# LM61495Q3_PINOUT.net
KiCad netlist of a schematic drawn in Altium Designer
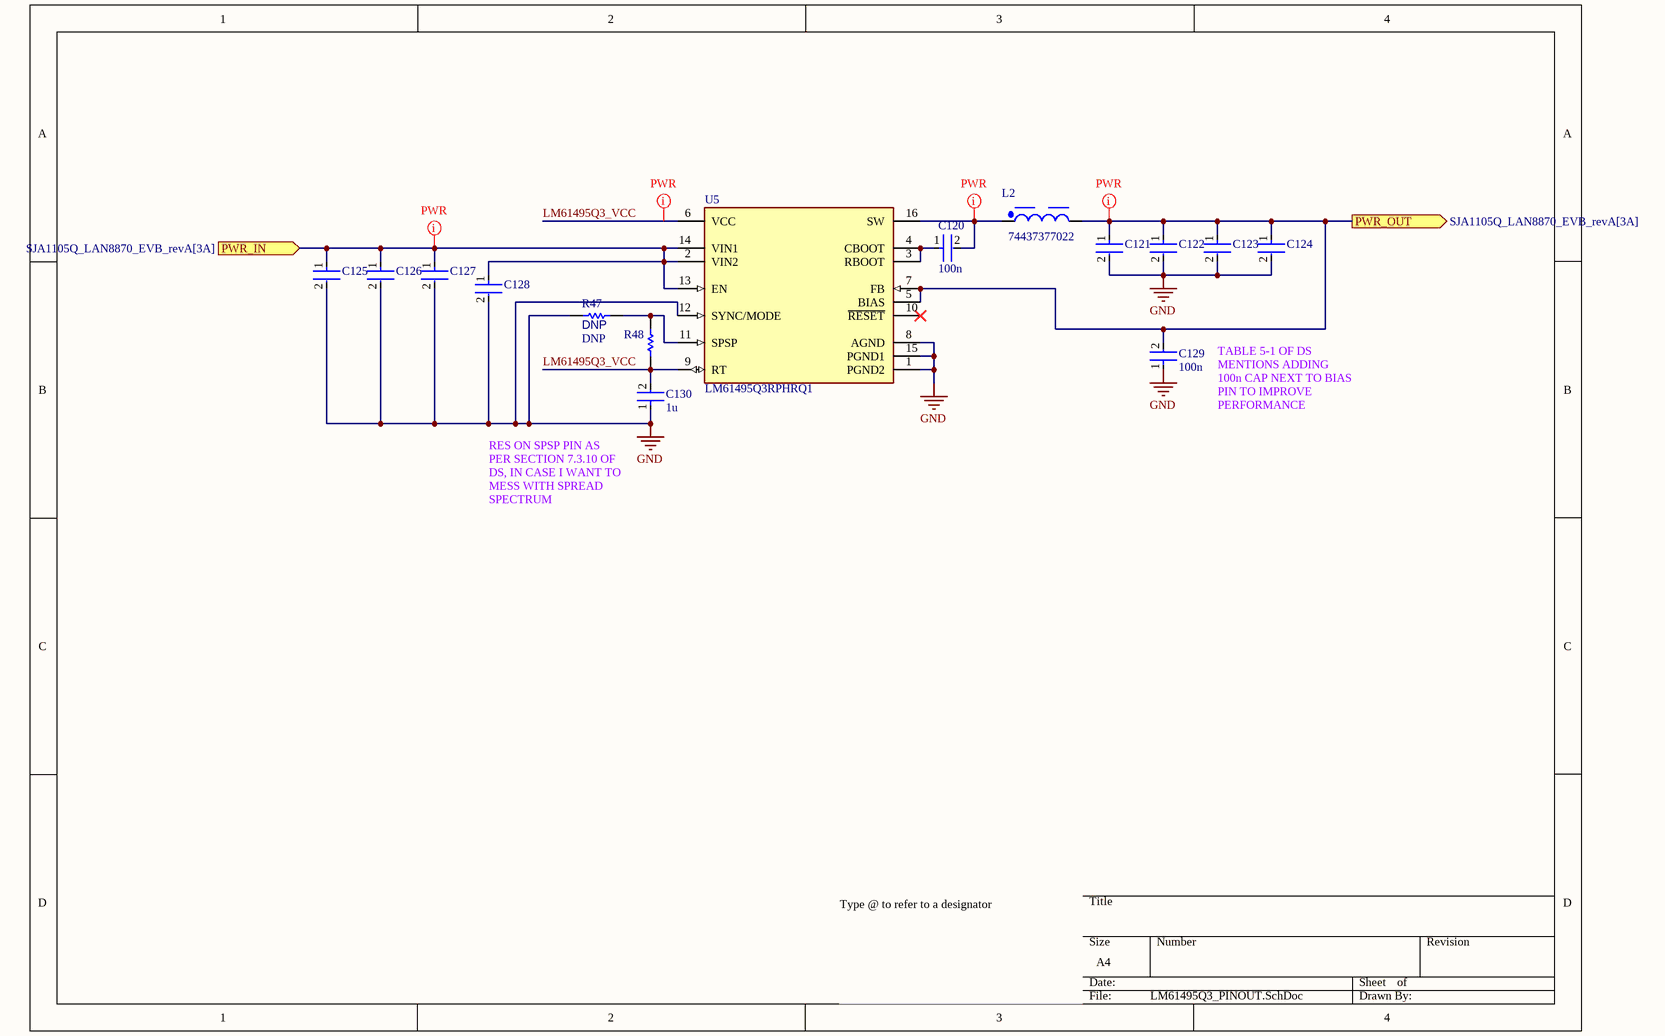
[diagram p0: LM61495Q3_PINOUT.SchDoc]

(export (version "E")
  (design (tool "Eeschema 10.0.6"))
  (components
    (comp (ref "C120")
      (value "100n")
      (footprint "FP-0402-L_1_0_0_05-W_0_5-IPC_A")
      (description "LARGE PADS, 0402 CAP, CHANGE COMMENT TO MATCH REAL P/N")
      (libsource (lib "Space Concordia") (part "b4654b650e69147ec39a6b967a45e02"))
    )
    (comp (ref "C121")
      (value "GRM32ER61C476KE15L")
      (footprint "FP-GRM32E-0_3-0_2-IPC_C")
      (description "CAP CER 47UF 16V X5R 1210")
      (fields (field (name "VOLTAGE") "16V") (field (name "TOLERANCE") "10%"))
      (libsource (lib "Altium Content Vault") (part "b4654b650e69147ec39a6b967a45e02"))
    )
    (comp (ref "C122")
      (value "GRM32ER61C476KE15L")
      (footprint "FP-GRM32E-0_3-0_2-IPC_C")
      (description "CAP CER 47UF 16V X5R 1210")
      (fields (field (name "VOLTAGE") "16V") (field (name "TOLERANCE") "10%"))
      (libsource (lib "Altium Content Vault") (part "b4654b650e69147ec39a6b967a45e02"))
    )
    (comp (ref "C123")
      (value "GRM32ER61C476KE15L")
      (footprint "FP-GRM32E-0_3-0_2-IPC_C")
      (description "CAP CER 47UF 16V X5R 1210")
      (fields (field (name "VOLTAGE") "16V") (field (name "TOLERANCE") "10%"))
      (libsource (lib "Altium Content Vault") (part "b4654b650e69147ec39a6b967a45e02"))
    )
    (comp (ref "C124")
      (value "DNP")
      (footprint "FP-GRM32E-0_3-0_2-IPC_C")
      (description "CAP CER 47UF 16V X5R 1210")
      (fields (field (name "VOLTAGE") "16V") (field (name "TOLERANCE") "10%"))
      (libsource (lib "Altium Content Vault") (part "b4654b650e69147ec39a6b967a45e02"))
    )
    (comp (ref "C125")
      (value "C3225X7R1H106M250AC")
      (footprint "FP-C3225-250-0_4-MFG")
      (description "Multilayer Ceramic Capacitors 10uF ±20% 50V X7R SMD 1210")
      (fields (field (name "TOLERANCE") "20%"))
      (libsource (lib "Altium Content Vault") (part "02cd4be3c70576c341d710602a673aa"))
    )
    (comp (ref "C126")
      (value "C3225X7R1H106M250AC")
      (footprint "FP-C3225-250-0_4-MFG")
      (description "Multilayer Ceramic Capacitors 10uF ±20% 50V X7R SMD 1210")
      (fields (field (name "TOLERANCE") "20%"))
      (libsource (lib "Altium Content Vault") (part "02cd4be3c70576c341d710602a673aa"))
    )
    (comp (ref "C127")
      (value "08055C474J4Z2A")
      (footprint "FP-0805-L_2_01_0_2-W_1_25-IPC_B")
      (description "Automotive Ceramic Capacitor, 0805, 470nF, 5%, X7R, 15%, 50V")
      (fields (field (name "TOLERANCE") "5%"))
      (libsource (lib "Altium Content Vault") (part "b4654b650e69147ec39a6b967a45e02"))
    )
    (comp (ref "C128")
      (value "08055C474J4Z2A")
      (footprint "FP-0805-L_2_01_0_2-W_1_25-IPC_B")
      (description "Automotive Ceramic Capacitor, 0805, 470nF, 5%, X7R, 15%, 50V")
      (fields (field (name "TOLERANCE") "5%"))
      (libsource (lib "Altium Content Vault") (part "b4654b650e69147ec39a6b967a45e02"))
    )
    (comp (ref "C129")
      (value "100n")
      (footprint "FP-0402-L_1_0_0_05-W_0_5-IPC_A")
      (description "LARGE PADS, 0402 CAP, CHANGE COMMENT TO MATCH REAL P/N")
      (libsource (lib "Space Concordia") (part "b4654b650e69147ec39a6b967a45e02"))
    )
    (comp (ref "C130")
      (value "1u")
      (footprint "FP-0402-L_1_0_0_05-W_0_5-IPC_A")
      (description "LARGE PADS, 0402 CAP, CHANGE COMMENT TO MATCH REAL P/N")
      (libsource (lib "Space Concordia") (part "b4654b650e69147ec39a6b967a45e02"))
    )
    (comp (ref "L2")
      (value "74437377022")
      (footprint "WE-LHMI_1335")
      (fields (field (name "TOLERANCE") "20%"))
      (libsource (lib "Altium Content Vault") (part "Inductor - 2"))
    )
    (comp (ref "R47")
      (value "DNP")
      (footprint "R0603B")
      (description "Resistor")
      (fields (field (name "ALTIUM_VALUE") "DNP"))
      (libsource (lib "Space Concordia") (part "Resistor"))
    )
    (comp (ref "R48")
      (value "0402 JUMPER")
      (footprint "RESC1005X40X25ML05T05")
      (description "READ THE NAME")
      (libsource (lib "Space Concordia") (part "CMP-009-00206-2"))
    )
    (comp (ref "U5")
      (value "LM61495Q3RPHRQ1")
      (footprint "FP-RPH0016A-MFG")
      (description "10-A AUTOMOTIVE BUCK CONVERTER O")
      (libsource (lib "Altium Content Vault") (part "be008cdd6a3ec40daeca3460eaab167"))
    )
  )
  (nets
    (net (code "1") (name "/LM61495Q3_VCC") (class "Default")
      (node (ref "C130") (pin "2") (pinfunction "2_2") (pintype "passive"))
      (node (ref "R48") (pin "1") (pinfunction "1_1") (pintype "passive"))
      (node (ref "U5") (pin "6") (pinfunction "VCC_6") (pintype "power_in"))
      (node (ref "U5") (pin "9") (pinfunction "RT_9") (pintype "bidirectional"))
    )
    (net (code "2") (name "/PWR_IN") (class "Default")
      (node (ref "C125") (pin "1") (pinfunction "1_1") (pintype "passive"))
      (node (ref "C126") (pin "1") (pinfunction "1_1") (pintype "passive"))
      (node (ref "C127") (pin "1") (pinfunction "1_1") (pintype "passive"))
      (node (ref "C128") (pin "1") (pinfunction "1_1") (pintype "passive"))
      (node (ref "U5") (pin "13") (pinfunction "EN_13") (pintype "input"))
      (node (ref "U5") (pin "14") (pinfunction "VIN1_14") (pintype "power_in"))
      (node (ref "U5") (pin "2") (pinfunction "VIN2_2") (pintype "power_in"))
    )
    (net (code "3") (name "/PWR_OUT") (class "Default")
      (node (ref "C121") (pin "1") (pinfunction "1_1") (pintype "passive"))
      (node (ref "C122") (pin "1") (pinfunction "1_1") (pintype "passive"))
      (node (ref "C123") (pin "1") (pinfunction "1_1") (pintype "passive"))
      (node (ref "C124") (pin "1") (pinfunction "1_1") (pintype "passive"))
      (node (ref "C129") (pin "2") (pinfunction "2_2") (pintype "passive"))
      (node (ref "L2") (pin "2") (pinfunction "2_2") (pintype "passive"))
      (node (ref "U5") (pin "5") (pinfunction "BIAS_5") (pintype "passive"))
      (node (ref "U5") (pin "7") (pinfunction "FB_7") (pintype "input"))
    )
    (net (code "4") (name "GND") (class "Default")
      (node (ref "C121") (pin "2") (pinfunction "2_2") (pintype "passive"))
      (node (ref "C122") (pin "2") (pinfunction "2_2") (pintype "passive"))
      (node (ref "C123") (pin "2") (pinfunction "2_2") (pintype "passive"))
      (node (ref "C124") (pin "2") (pinfunction "2_2") (pintype "passive"))
      (node (ref "C125") (pin "2") (pinfunction "2_2") (pintype "passive"))
      (node (ref "C126") (pin "2") (pinfunction "2_2") (pintype "passive"))
      (node (ref "C127") (pin "2") (pinfunction "2_2") (pintype "passive"))
      (node (ref "C128") (pin "2") (pinfunction "2_2") (pintype "passive"))
      (node (ref "C129") (pin "1") (pinfunction "1_1") (pintype "passive"))
      (node (ref "C130") (pin "1") (pinfunction "1_1") (pintype "passive"))
      (node (ref "R47") (pin "2") (pinfunction "2_2") (pintype "passive"))
      (node (ref "U5") (pin "1") (pinfunction "PGND2_1") (pintype "power_in"))
      (node (ref "U5") (pin "12") (pinfunction "SYNC/MODE_12") (pintype "input"))
      (node (ref "U5") (pin "15") (pinfunction "PGND1_15") (pintype "power_in"))
      (node (ref "U5") (pin "8") (pinfunction "AGND_8") (pintype "power_in"))
    )
    (net (code "5") (name "Net-(U5-CBOOT)") (class "Default")
      (node (ref "C120") (pin "1") (pinfunction "1_1") (pintype "passive"))
      (node (ref "U5") (pin "3") (pinfunction "RBOOT_3") (pintype "power_in"))
      (node (ref "U5") (pin "4") (pinfunction "CBOOT_4") (pintype "power_in"))
    )
    (net (code "6") (name "Net-(U5-SPSP)") (class "Default")
      (node (ref "R47") (pin "1") (pinfunction "1_1") (pintype "passive"))
      (node (ref "R48") (pin "2") (pinfunction "2_2") (pintype "passive"))
      (node (ref "U5") (pin "11") (pinfunction "SPSP_11") (pintype "input"))
    )
    (net (code "7") (name "Net-(U5-SW)") (class "Default")
      (node (ref "C120") (pin "2") (pinfunction "2_2") (pintype "passive"))
      (node (ref "L2") (pin "1") (pinfunction "1_1") (pintype "passive"))
      (node (ref "U5") (pin "16") (pinfunction "SW_16") (pintype "power_in"))
    )
    (net (code "8") (name "unconnected-(U5-~{RESET}-Pad10)") (class "Default")
      (node (ref "U5") (pin "10") (pinfunction "~{RESET}_10") (pintype "open_collector+no_connect"))
    )
  )
)
